# LPC1115_4TE_TOP_V1_0.net
KiCad netlist of a schematic drawn in EAGLE
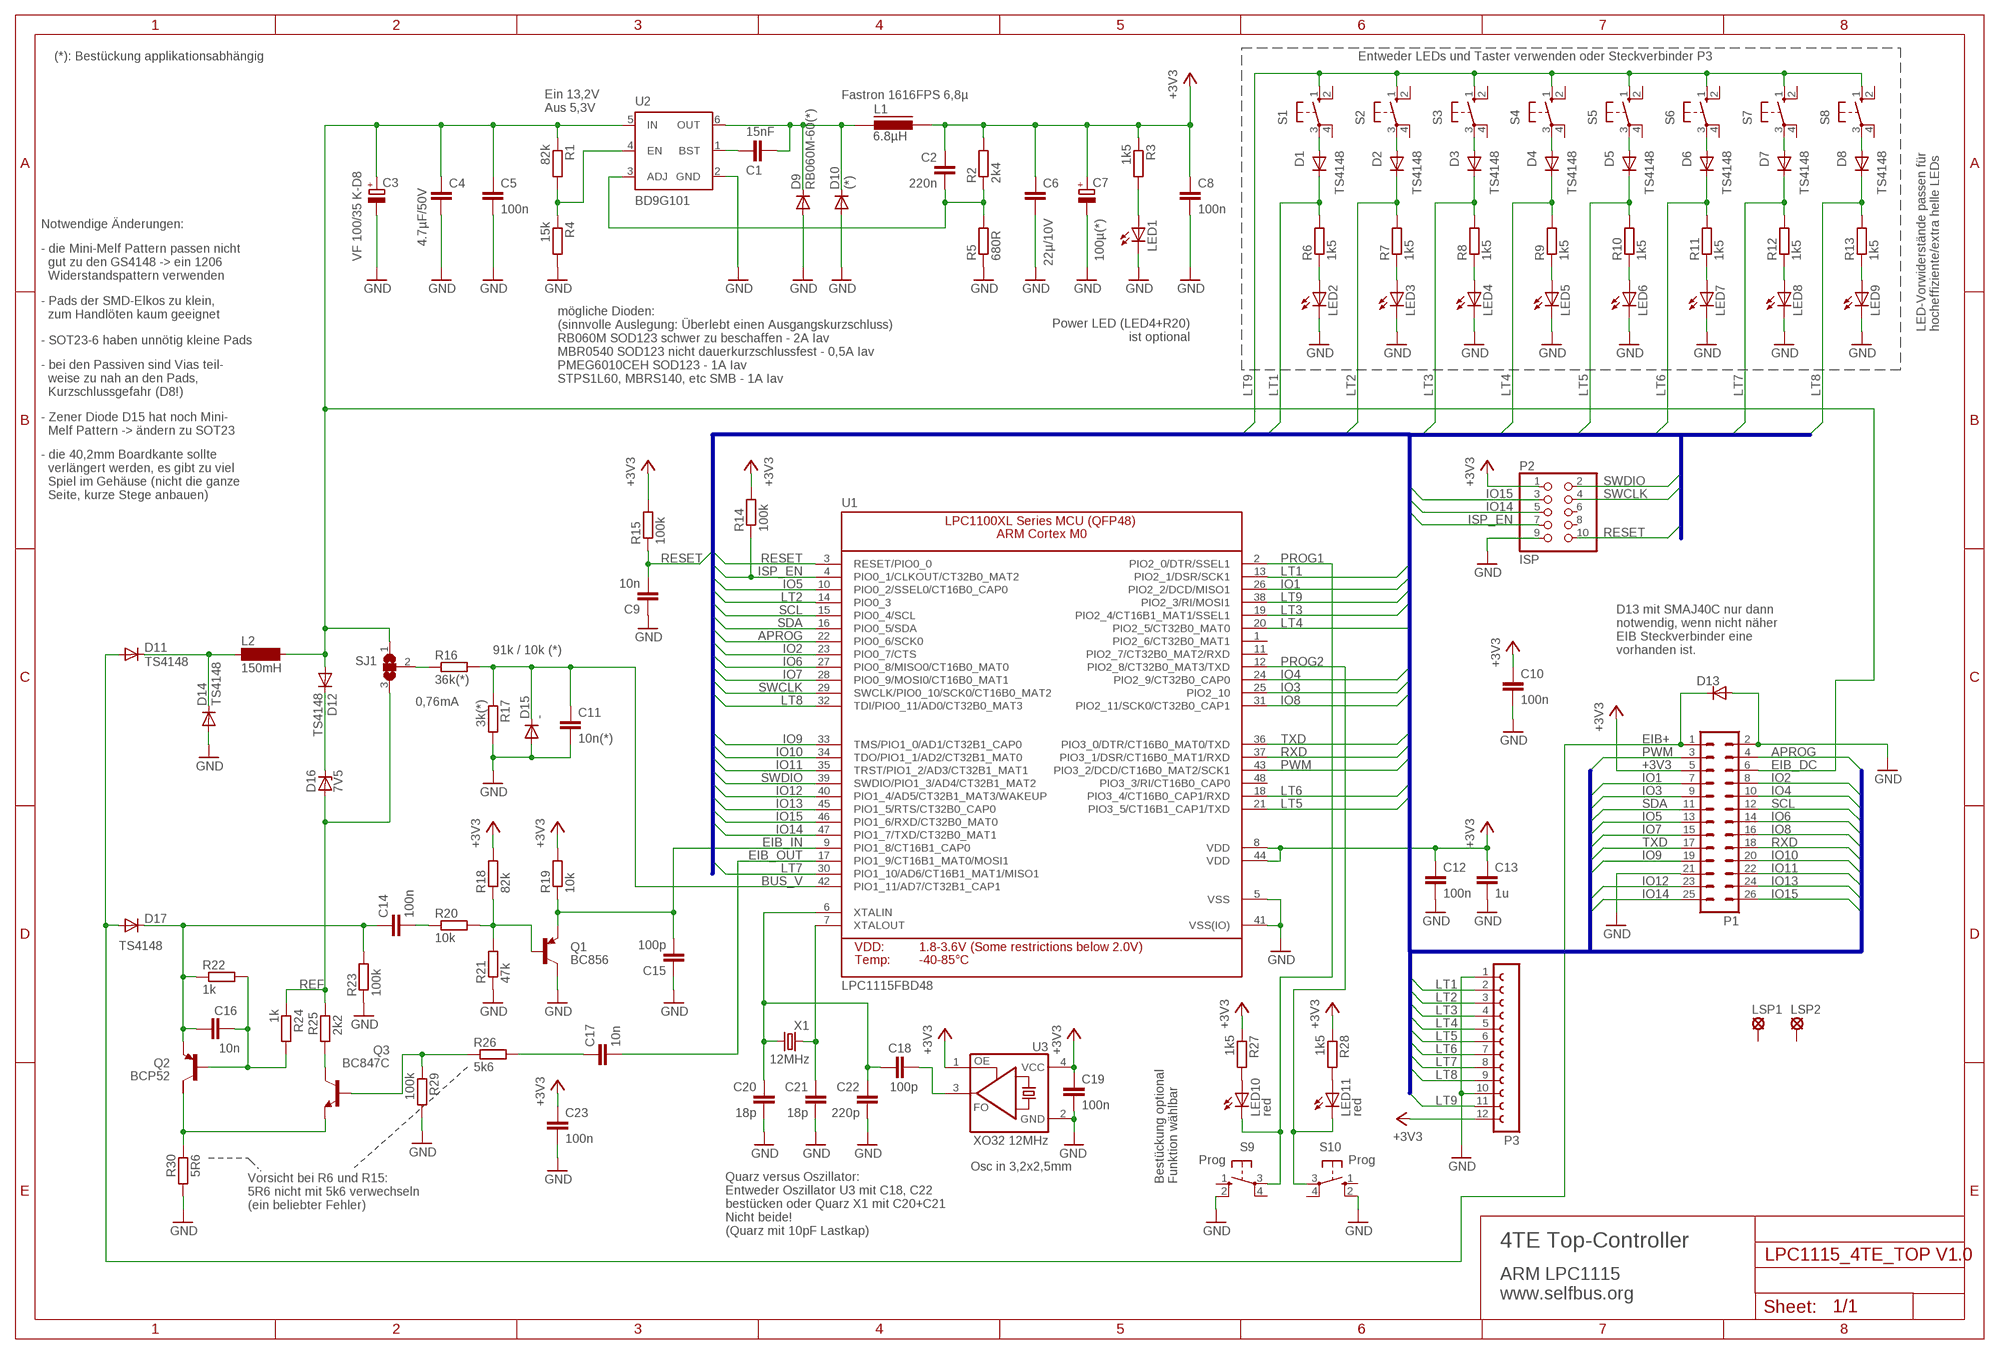
[diagram p0: schematic, sheet 1]

(export (version "E")
  (design (tool "Eeschema 10.0.6"))
  (components
    (comp (ref "C1")
      (value "15nF")
      (footprint "eagle-import:R0805M")
      (libsource (lib "eagle-import") (part "C-EUC0805M"))
    )
    (comp (ref "C2")
      (value "220n")
      (footprint "eagle-import:R0805M")
      (libsource (lib "eagle-import") (part "C-EUC0805M"))
    )
    (comp (ref "C3")
      (value "VF 100/35 K-D8")
      (footprint "eagle-import:UD-6,3X7,7_NICHICON")
      (libsource (lib "eagle-import") (part "CPOL-EUUD-6,3X7,7"))
    )
    (comp (ref "C4")
      (value "4.7µF/50V")
      (footprint "eagle-import:R1206M")
      (libsource (lib "eagle-import") (part "C-EUC1206M"))
    )
    (comp (ref "C5")
      (value "100n")
      (footprint "eagle-import:R0805M")
      (libsource (lib "eagle-import") (part "C-EUC0805M"))
    )
    (comp (ref "C6")
      (value "22µ/10V")
      (footprint "eagle-import:C1210K")
      (libsource (lib "eagle-import") (part "C-EUC1210K"))
    )
    (comp (ref "C7")
      (value "100µ(*)")
      (footprint "eagle-import:UD-6,3X7,7_NICHICON")
      (libsource (lib "eagle-import") (part "CPOL-EUUD-6,3X7,7"))
    )
    (comp (ref "C8")
      (value "100n")
      (footprint "eagle-import:R0805M")
      (libsource (lib "eagle-import") (part "C-EUC0805M"))
    )
    (comp (ref "C9")
      (value "10n")
      (footprint "eagle-import:R0805M")
      (libsource (lib "eagle-import") (part "C-EUC0805M"))
    )
    (comp (ref "C10")
      (value "100n")
      (footprint "eagle-import:R0805M")
      (libsource (lib "eagle-import") (part "C-EUC0805M"))
    )
    (comp (ref "C11")
      (value "10n(*)")
      (footprint "eagle-import:R0805M")
      (libsource (lib "eagle-import") (part "C-EUC0805M"))
    )
    (comp (ref "C12")
      (value "100n")
      (footprint "eagle-import:R0805M")
      (libsource (lib "eagle-import") (part "C-EUC0805M"))
    )
    (comp (ref "C13")
      (value "1u")
      (footprint "eagle-import:R0805M")
      (libsource (lib "eagle-import") (part "C-EUC0805M"))
    )
    (comp (ref "C14")
      (value "100n")
      (footprint "eagle-import:R0805M")
      (libsource (lib "eagle-import") (part "C-EUC0805M"))
    )
    (comp (ref "C15")
      (value "100p")
      (footprint "eagle-import:R0805M")
      (libsource (lib "eagle-import") (part "C-EUC0805M"))
    )
    (comp (ref "C16")
      (value "10n")
      (footprint "eagle-import:R0805M")
      (libsource (lib "eagle-import") (part "C-EUC0805M"))
    )
    (comp (ref "C17")
      (value "10n")
      (footprint "eagle-import:R0805M")
      (libsource (lib "eagle-import") (part "C-EUC0805M"))
    )
    (comp (ref "C18")
      (value "100p")
      (footprint "eagle-import:R0805M")
      (libsource (lib "eagle-import") (part "C-EUC0805M"))
    )
    (comp (ref "C19")
      (value "100n")
      (footprint "eagle-import:R0805M")
      (libsource (lib "eagle-import") (part "C-EUC0805M"))
    )
    (comp (ref "C20")
      (value "18p")
      (footprint "eagle-import:R0805M")
      (libsource (lib "eagle-import") (part "C-EUC0805M"))
    )
    (comp (ref "C21")
      (value "18p")
      (footprint "eagle-import:R0805M")
      (libsource (lib "eagle-import") (part "C-EUC0805M"))
    )
    (comp (ref "C22")
      (value "220p")
      (footprint "eagle-import:R0805M")
      (libsource (lib "eagle-import") (part "C-EUC0805M"))
    )
    (comp (ref "C23")
      (value "100n")
      (footprint "eagle-import:R0805M")
      (libsource (lib "eagle-import") (part "C-EUC0805M"))
    )
    (comp (ref "D1")
      (value "TS4148")
      (footprint "eagle-import:MINIMELF")
      (libsource (lib "eagle-import") (part "DIODE-MINIMELF"))
    )
    (comp (ref "D2")
      (value "TS4148")
      (footprint "eagle-import:MINIMELF")
      (libsource (lib "eagle-import") (part "DIODE-MINIMELF"))
    )
    (comp (ref "D3")
      (value "TS4148")
      (footprint "eagle-import:MINIMELF")
      (libsource (lib "eagle-import") (part "DIODE-MINIMELF"))
    )
    (comp (ref "D4")
      (value "TS4148")
      (footprint "eagle-import:MINIMELF")
      (libsource (lib "eagle-import") (part "DIODE-MINIMELF"))
    )
    (comp (ref "D5")
      (value "TS4148")
      (footprint "eagle-import:MINIMELF")
      (libsource (lib "eagle-import") (part "DIODE-MINIMELF"))
    )
    (comp (ref "D6")
      (value "TS4148")
      (footprint "eagle-import:MINIMELF")
      (libsource (lib "eagle-import") (part "DIODE-MINIMELF"))
    )
    (comp (ref "D7")
      (value "TS4148")
      (footprint "eagle-import:MINIMELF")
      (libsource (lib "eagle-import") (part "DIODE-MINIMELF"))
    )
    (comp (ref "D8")
      (value "TS4148")
      (footprint "eagle-import:MINIMELF")
      (libsource (lib "eagle-import") (part "DIODE-MINIMELF"))
    )
    (comp (ref "D9")
      (value "RB060M-60(*)")
      (footprint "eagle-import:SOD123")
      (libsource (lib "eagle-import") (part "DIODE-SOD123"))
    )
    (comp (ref "D10")
      (value "(*)")
      (footprint "eagle-import:SMB")
      (libsource (lib "eagle-import") (part "DIODE-SMB"))
    )
    (comp (ref "D11")
      (value "TS4148")
      (footprint "eagle-import:MINIMELF")
      (libsource (lib "eagle-import") (part "DIODE-MINIMELF"))
    )
    (comp (ref "D12")
      (value "TS4148")
      (footprint "eagle-import:MINIMELF")
      (libsource (lib "eagle-import") (part "DIODE-MINIMELF"))
    )
    (comp (ref "D13")
      (value "D-SMB")
      (footprint "eagle-import:SMB")
      (libsource (lib "eagle-import") (part "D-SMB"))
    )
    (comp (ref "D14")
      (value "TS4148")
      (footprint "eagle-import:MINIMELF")
      (libsource (lib "eagle-import") (part "DIODE-MINIMELF"))
    )
    (comp (ref "D15")
      (value "-")
      (footprint "eagle-import:MINIMELF")
      (libsource (lib "eagle-import") (part "DIODE-MINIMELF"))
    )
    (comp (ref "D16")
      (value "7V5")
      (footprint "eagle-import:SOT23")
      (libsource (lib "eagle-import") (part "ZENER-DIODESOT23"))
    )
    (comp (ref "D17")
      (value "TS4148")
      (footprint "eagle-import:MINIMELF")
      (libsource (lib "eagle-import") (part "DIODE-MINIMELF"))
    )
    (comp (ref "L1")
      (value "6.8µH")
      (footprint "eagle-import:1616FPS")
      (libsource (lib "eagle-import") (part "IND_FASTRON_1616FPSB"))
    )
    (comp (ref "L2")
      (value "150mH")
      (footprint "eagle-import:BS11_LIEGEND")
      (libsource (lib "eagle-import") (part "SD12BS11_LIEGEND"))
    )
    (comp (ref "LED1")
      (value "LEDSMT1206")
      (footprint "eagle-import:1206")
      (libsource (lib "eagle-import") (part "LEDSMT1206"))
    )
    (comp (ref "LED2")
      (value "LEDSMT1206")
      (footprint "eagle-import:1206")
      (libsource (lib "eagle-import") (part "LEDSMT1206"))
    )
    (comp (ref "LED3")
      (value "LEDSMT1206")
      (footprint "eagle-import:1206")
      (libsource (lib "eagle-import") (part "LEDSMT1206"))
    )
    (comp (ref "LED4")
      (value "LEDSMT1206")
      (footprint "eagle-import:1206")
      (libsource (lib "eagle-import") (part "LEDSMT1206"))
    )
    (comp (ref "LED5")
      (value "LEDSMT1206")
      (footprint "eagle-import:1206")
      (libsource (lib "eagle-import") (part "LEDSMT1206"))
    )
    (comp (ref "LED6")
      (value "LEDSMT1206")
      (footprint "eagle-import:1206")
      (libsource (lib "eagle-import") (part "LEDSMT1206"))
    )
    (comp (ref "LED7")
      (value "LEDSMT1206")
      (footprint "eagle-import:1206")
      (libsource (lib "eagle-import") (part "LEDSMT1206"))
    )
    (comp (ref "LED8")
      (value "LEDSMT1206")
      (footprint "eagle-import:1206")
      (libsource (lib "eagle-import") (part "LEDSMT1206"))
    )
    (comp (ref "LED9")
      (value "LEDSMT1206")
      (footprint "eagle-import:1206")
      (libsource (lib "eagle-import") (part "LEDSMT1206"))
    )
    (comp (ref "LED10")
      (value "red")
      (footprint "eagle-import:1206")
      (libsource (lib "eagle-import") (part "LEDSMT1206"))
    )
    (comp (ref "LED11")
      (value "red")
      (footprint "eagle-import:1206")
      (libsource (lib "eagle-import") (part "LEDSMT1206"))
    )
    (comp (ref "LSP1")
      (value "SE13_SM")
      (footprint "eagle-import:SE13_SM")
      (libsource (lib "eagle-import") (part "SE13_SM"))
    )
    (comp (ref "LSP2")
      (value "SE13_SM")
      (footprint "eagle-import:SE13_SM")
      (libsource (lib "eagle-import") (part "SE13_SM"))
    )
    (comp (ref "P1")
      (value "ML26")
      (footprint "eagle-import:ML26")
      (libsource (lib "eagle-import") (part "ML26"))
    )
    (comp (ref "P2")
      (value "ISP")
      (footprint "eagle-import:2X05M")
      (libsource (lib "eagle-import") (part "PINHD-2X05_2.00"))
    )
    (comp (ref "P3")
      (value "FE12-1")
      (footprint "eagle-import:FE12")
      (libsource (lib "eagle-import") (part "FE12-1"))
    )
    (comp (ref "Q1")
      (value "BC856")
      (footprint "eagle-import:SOT23-BEC")
      (libsource (lib "eagle-import") (part "BC856SMDB"))
    )
    (comp (ref "Q2")
      (value "BCP52")
      (footprint "eagle-import:SOT223")
      (libsource (lib "eagle-import") (part "FZT753SMD"))
    )
    (comp (ref "Q3")
      (value "BC847C")
      (footprint "eagle-import:SOT23")
      (libsource (lib "eagle-import") (part "BC847"))
    )
    (comp (ref "R1")
      (value "82k")
      (footprint "eagle-import:R0805M")
      (libsource (lib "eagle-import") (part "R-EU_R0805M"))
    )
    (comp (ref "R2")
      (value "2k4")
      (footprint "eagle-import:R0805M")
      (libsource (lib "eagle-import") (part "R-EU_R0805M"))
    )
    (comp (ref "R3")
      (value "1k5")
      (footprint "eagle-import:R0805M")
      (libsource (lib "eagle-import") (part "R-EU_R0805M"))
    )
    (comp (ref "R4")
      (value "15k")
      (footprint "eagle-import:R0805M")
      (libsource (lib "eagle-import") (part "R-EU_R0805M"))
    )
    (comp (ref "R5")
      (value "680R")
      (footprint "eagle-import:R0805M")
      (libsource (lib "eagle-import") (part "R-EU_R0805M"))
    )
    (comp (ref "R6")
      (value "1k5")
      (footprint "eagle-import:R0805M")
      (libsource (lib "eagle-import") (part "R-EU_R0805M"))
    )
    (comp (ref "R7")
      (value "1k5")
      (footprint "eagle-import:R0805M")
      (libsource (lib "eagle-import") (part "R-EU_R0805M"))
    )
    (comp (ref "R8")
      (value "1k5")
      (footprint "eagle-import:R0805M")
      (libsource (lib "eagle-import") (part "R-EU_R0805M"))
    )
    (comp (ref "R9")
      (value "1k5")
      (footprint "eagle-import:R0805M")
      (libsource (lib "eagle-import") (part "R-EU_R0805M"))
    )
    (comp (ref "R10")
      (value "1k5")
      (footprint "eagle-import:R0805M")
      (libsource (lib "eagle-import") (part "R-EU_R0805M"))
    )
    (comp (ref "R11")
      (value "1k5")
      (footprint "eagle-import:R0805M")
      (libsource (lib "eagle-import") (part "R-EU_R0805M"))
    )
    (comp (ref "R12")
      (value "1k5")
      (footprint "eagle-import:R0805M")
      (libsource (lib "eagle-import") (part "R-EU_R0805M"))
    )
    (comp (ref "R13")
      (value "1k5")
      (footprint "eagle-import:R0805M")
      (libsource (lib "eagle-import") (part "R-EU_R0805M"))
    )
    (comp (ref "R14")
      (value "100k")
      (footprint "eagle-import:R0805M")
      (libsource (lib "eagle-import") (part "R-EU_R0805M"))
    )
    (comp (ref "R15")
      (value "100k")
      (footprint "eagle-import:R0805M")
      (libsource (lib "eagle-import") (part "R-EU_R0805M"))
    )
    (comp (ref "R16")
      (value "36k(*)")
      (footprint "eagle-import:R0805M")
      (libsource (lib "eagle-import") (part "R-EU_R0805M"))
    )
    (comp (ref "R17")
      (value "3k(*)")
      (footprint "eagle-import:R0805M")
      (libsource (lib "eagle-import") (part "R-EU_R0805M"))
    )
    (comp (ref "R18")
      (value "82k")
      (footprint "eagle-import:R0805M")
      (libsource (lib "eagle-import") (part "R-EU_R0805M"))
    )
    (comp (ref "R19")
      (value "10k")
      (footprint "eagle-import:R0805M")
      (libsource (lib "eagle-import") (part "R-EU_R0805M"))
    )
    (comp (ref "R20")
      (value "10k")
      (footprint "eagle-import:R0805M")
      (libsource (lib "eagle-import") (part "R-EU_R0805M"))
    )
    (comp (ref "R21")
      (value "47k")
      (footprint "eagle-import:R0805M")
      (libsource (lib "eagle-import") (part "R-EU_R0805M"))
    )
    (comp (ref "R22")
      (value "1k")
      (footprint "eagle-import:R0805M")
      (libsource (lib "eagle-import") (part "R-EU_R0805M"))
    )
    (comp (ref "R23")
      (value "100k")
      (footprint "eagle-import:R0805M")
      (libsource (lib "eagle-import") (part "R-EU_R0805M"))
    )
    (comp (ref "R24")
      (value "1k")
      (footprint "eagle-import:R0805M")
      (libsource (lib "eagle-import") (part "R-EU_R0805M"))
    )
    (comp (ref "R25")
      (value "2k2")
      (footprint "eagle-import:R0805M")
      (libsource (lib "eagle-import") (part "R-EU_R0805M"))
    )
    (comp (ref "R26")
      (value "5k6")
      (footprint "eagle-import:R0805M")
      (libsource (lib "eagle-import") (part "R-EU_R0805M"))
    )
    (comp (ref "R27")
      (value "1k5")
      (footprint "eagle-import:R0805M")
      (libsource (lib "eagle-import") (part "R-EU_R0805M"))
    )
    (comp (ref "R28")
      (value "1k5")
      (footprint "eagle-import:R0805M")
      (libsource (lib "eagle-import") (part "R-EU_R0805M"))
    )
    (comp (ref "R29")
      (value "100k")
      (footprint "eagle-import:R0805M")
      (libsource (lib "eagle-import") (part "R-EU_R0805M"))
    )
    (comp (ref "R30")
      (value "5R6")
      (footprint "eagle-import:R1206M")
      (libsource (lib "eagle-import") (part "R-EU_R1206M"))
    )
    (comp (ref "S1")
      (value "10-XXSMD")
      (footprint "eagle-import:B3F-10XX_SMD")
      (libsource (lib "eagle-import") (part "10-XXSMD"))
    )
    (comp (ref "S2")
      (value "10-XXSMD")
      (footprint "eagle-import:B3F-10XX_SMD")
      (libsource (lib "eagle-import") (part "10-XXSMD"))
    )
    (comp (ref "S3")
      (value "10-XXSMD")
      (footprint "eagle-import:B3F-10XX_SMD")
      (libsource (lib "eagle-import") (part "10-XXSMD"))
    )
    (comp (ref "S4")
      (value "10-XXSMD")
      (footprint "eagle-import:B3F-10XX_SMD")
      (libsource (lib "eagle-import") (part "10-XXSMD"))
    )
    (comp (ref "S5")
      (value "10-XXSMD")
      (footprint "eagle-import:B3F-10XX_SMD")
      (libsource (lib "eagle-import") (part "10-XXSMD"))
    )
    (comp (ref "S6")
      (value "10-XXSMD")
      (footprint "eagle-import:B3F-10XX_SMD")
      (libsource (lib "eagle-import") (part "10-XXSMD"))
    )
    (comp (ref "S7")
      (value "10-XXSMD")
      (footprint "eagle-import:B3F-10XX_SMD")
      (libsource (lib "eagle-import") (part "10-XXSMD"))
    )
    (comp (ref "S8")
      (value "10-XXSMD")
      (footprint "eagle-import:B3F-10XX_SMD")
      (libsource (lib "eagle-import") (part "10-XXSMD"))
    )
    (comp (ref "S9")
      (value "Prog")
      (footprint "eagle-import:B3F-10XX_SMD")
      (libsource (lib "eagle-import") (part "10-XXSMD"))
    )
    (comp (ref "S10")
      (value "Prog")
      (footprint "eagle-import:B3F-10XX_SMD")
      (libsource (lib "eagle-import") (part "10-XXSMD"))
    )
    (comp (ref "SJ1")
      (value "SJ2W")
      (footprint "eagle-import:SJ_2")
      (libsource (lib "eagle-import") (part "SJ2W"))
    )
    (comp (ref "U1")
      (value "LPC1115FBD48")
      (footprint "eagle-import:LQFP48")
      (libsource (lib "eagle-import") (part "LPC1113/4/5_QFP48_XLSERIES"))
    )
    (comp (ref "U2")
      (value "BD9G101")
      (footprint "eagle-import:SOT23-6")
      (libsource (lib "eagle-import") (part "BD9G101GBD9G101G-SOT23-6"))
    )
    (comp (ref "U3")
      (value "XO32 12MHz")
      (footprint "eagle-import:ASF")
      (libsource (lib "eagle-import") (part "ASFL"))
    )
    (comp (ref "X1")
      (value "12MHz")
      (footprint "eagle-import:ASF")
      (libsource (lib "eagle-import") (part "CRYSTALASF"))
    )
  )
  (nets
    (net (code "1") (name "+3V3") (class "Default")
      (node (ref "C10") (pin "1") (pinfunction "1_1") (pintype "passive"))
      (node (ref "C12") (pin "1") (pinfunction "1_1") (pintype "passive"))
      (node (ref "C13") (pin "1") (pinfunction "1_1") (pintype "passive"))
      (node (ref "C19") (pin "1") (pinfunction "1_1") (pintype "passive"))
      (node (ref "C2") (pin "1") (pinfunction "1_1") (pintype "passive"))
      (node (ref "C23") (pin "1") (pinfunction "1_1") (pintype "passive"))
      (node (ref "C6") (pin "1") (pinfunction "1_1") (pintype "passive"))
      (node (ref "C7") (pin "+") (pinfunction "+_+") (pintype "passive"))
      (node (ref "C8") (pin "1") (pinfunction "1_1") (pintype "passive"))
      (node (ref "L1") (pin "P$2") (pinfunction "2_P$2") (pintype "passive"))
      (node (ref "P1") (pin "5") (pinfunction "5_5") (pintype "passive"))
      (node (ref "P2") (pin "1") (pinfunction "1_1") (pintype "passive"))
      (node (ref "P3") (pin "12") (pinfunction "12_12") (pintype "passive"))
      (node (ref "R14") (pin "2") (pinfunction "2_2") (pintype "passive"))
      (node (ref "R15") (pin "2") (pinfunction "2_2") (pintype "passive"))
      (node (ref "R18") (pin "2") (pinfunction "2_2") (pintype "passive"))
      (node (ref "R19") (pin "2") (pinfunction "2_2") (pintype "passive"))
      (node (ref "R2") (pin "2") (pinfunction "2_2") (pintype "passive"))
      (node (ref "R27") (pin "1") (pinfunction "1_1") (pintype "passive"))
      (node (ref "R28") (pin "1") (pinfunction "1_1") (pintype "passive"))
      (node (ref "R3") (pin "1") (pinfunction "1_1") (pintype "passive"))
      (node (ref "U1") (pin "44") (pinfunction "VDD_44") (pintype "power_in"))
      (node (ref "U1") (pin "8") (pinfunction "VDD_8") (pintype "power_in"))
      (node (ref "U3") (pin "1") (pinfunction "OE_1") (pintype "input"))
      (node (ref "U3") (pin "4") (pinfunction "VCC_4") (pintype "power_in"))
    )
    (net (code "2") (name "/APROG") (class "Default")
      (node (ref "P1") (pin "4") (pinfunction "4_4") (pintype "passive"))
      (node (ref "U1") (pin "22") (pinfunction "PIO0_6/SCK0_22") (pintype "bidirectional"))
    )
    (net (code "3") (name "/BUS_V") (class "Default")
      (node (ref "C11") (pin "1") (pinfunction "1_1") (pintype "passive"))
      (node (ref "D15") (pin "C") (pinfunction "C_C") (pintype "passive"))
      (node (ref "R16") (pin "2") (pinfunction "2_2") (pintype "passive"))
      (node (ref "R17") (pin "1") (pinfunction "1_1") (pintype "passive"))
      (node (ref "U1") (pin "42") (pinfunction "PIO1_11/AD7/CT32B1_CAP1_42") (pintype "bidirectional"))
    )
    (net (code "4") (name "/EIB+") (class "Default")
      (node (ref "D11") (pin "A") (pinfunction "A_A") (pintype "passive"))
      (node (ref "D13") (pin "1") (pinfunction "C_1") (pintype "passive"))
      (node (ref "D17") (pin "A") (pinfunction "A_A") (pintype "passive"))
      (node (ref "P1") (pin "1") (pinfunction "1_1") (pintype "passive"))
    )
    (net (code "5") (name "/EIB_DC") (class "Default")
      (node (ref "C3") (pin "+") (pinfunction "+_+") (pintype "passive"))
      (node (ref "C4") (pin "1") (pinfunction "1_1") (pintype "passive"))
      (node (ref "C5") (pin "1") (pinfunction "1_1") (pintype "passive"))
      (node (ref "D12") (pin "A") (pinfunction "A_A") (pintype "passive"))
      (node (ref "L2") (pin "2") (pinfunction "2_2") (pintype "passive"))
      (node (ref "P1") (pin "6") (pinfunction "6_6") (pintype "passive"))
      (node (ref "R1") (pin "1") (pinfunction "1_1") (pintype "passive"))
      (node (ref "SJ1") (pin "1") (pinfunction "1_1") (pintype "passive"))
      (node (ref "U2") (pin "5") (pinfunction "IN_5") (pintype "input"))
    )
    (net (code "6") (name "/EIB_IN") (class "Default")
      (node (ref "C15") (pin "2") (pinfunction "2_2") (pintype "passive"))
      (node (ref "Q1") (pin "E") (pinfunction "E_E") (pintype "passive"))
      (node (ref "R19") (pin "1") (pinfunction "1_1") (pintype "passive"))
      (node (ref "U1") (pin "9") (pinfunction "PIO1_8/CT16B1_CAP0_9") (pintype "bidirectional"))
    )
    (net (code "7") (name "/EIB_OUT") (class "Default")
      (node (ref "C17") (pin "2") (pinfunction "2_2") (pintype "passive"))
      (node (ref "U1") (pin "17") (pinfunction "PIO1_9/CT16B1_MAT0/MOSI1_17") (pintype "bidirectional"))
    )
    (net (code "8") (name "/IO1") (class "Default")
      (node (ref "P1") (pin "7") (pinfunction "7_7") (pintype "passive"))
      (node (ref "U1") (pin "26") (pinfunction "PIO2_2/DCD/MISO1_26") (pintype "bidirectional"))
    )
    (net (code "9") (name "/IO2") (class "Default")
      (node (ref "P1") (pin "8") (pinfunction "8_8") (pintype "passive"))
      (node (ref "U1") (pin "23") (pinfunction "PIO0_7/CTS_23") (pintype "bidirectional"))
    )
    (net (code "10") (name "/IO3") (class "Default")
      (node (ref "P1") (pin "9") (pinfunction "9_9") (pintype "passive"))
      (node (ref "U1") (pin "25") (pinfunction "PIO2_10_25") (pintype "bidirectional"))
    )
    (net (code "11") (name "/IO4") (class "Default")
      (node (ref "P1") (pin "10") (pinfunction "10_10") (pintype "passive"))
      (node (ref "U1") (pin "24") (pinfunction "PIO2_9/CT32B0_CAP0_24") (pintype "bidirectional"))
    )
    (net (code "12") (name "/IO5") (class "Default")
      (node (ref "P1") (pin "13") (pinfunction "13_13") (pintype "passive"))
      (node (ref "U1") (pin "10") (pinfunction "PIO0_2/SSEL0/CT16B0_CAP0_10") (pintype "bidirectional"))
    )
    (net (code "13") (name "/IO6") (class "Default")
      (node (ref "P1") (pin "14") (pinfunction "14_14") (pintype "passive"))
      (node (ref "U1") (pin "27") (pinfunction "PIO0_8/MISO0/CT16B0_MAT0_27") (pintype "bidirectional"))
    )
    (net (code "14") (name "/IO7") (class "Default")
      (node (ref "P1") (pin "15") (pinfunction "15_15") (pintype "passive"))
      (node (ref "U1") (pin "28") (pinfunction "PIO0_9/MOSI0/CT16B0_MAT1_28") (pintype "bidirectional"))
    )
    (net (code "15") (name "/IO8") (class "Default")
      (node (ref "P1") (pin "16") (pinfunction "16_16") (pintype "passive"))
      (node (ref "U1") (pin "31") (pinfunction "PIO2_11/SCK0/CT32B0_CAP1_31") (pintype "bidirectional"))
    )
    (net (code "16") (name "/IO9") (class "Default")
      (node (ref "P1") (pin "19") (pinfunction "19_19") (pintype "passive"))
      (node (ref "U1") (pin "33") (pinfunction "TMS/PIO1_0/AD1/CT32B1_CAP0_33") (pintype "bidirectional"))
    )
    (net (code "17") (name "/IO10") (class "Default")
      (node (ref "P1") (pin "20") (pinfunction "20_20") (pintype "passive"))
      (node (ref "U1") (pin "34") (pinfunction "TDO/PIO1_1/AD2/CT32B1_MAT0_34") (pintype "bidirectional"))
    )
    (net (code "18") (name "/IO11") (class "Default")
      (node (ref "P1") (pin "22") (pinfunction "22_22") (pintype "passive"))
      (node (ref "U1") (pin "35") (pinfunction "TRST/PIO1_2/AD3/CT32B1_MAT1_35") (pintype "bidirectional"))
    )
    (net (code "19") (name "/IO12") (class "Default")
      (node (ref "P1") (pin "23") (pinfunction "23_23") (pintype "passive"))
      (node (ref "U1") (pin "40") (pinfunction "PIO1_4/AD5/CT32B1_MAT3/WAKEUP_40") (pintype "bidirectional"))
    )
    (net (code "20") (name "/IO13") (class "Default")
      (node (ref "P1") (pin "24") (pinfunction "24_24") (pintype "passive"))
      (node (ref "U1") (pin "45") (pinfunction "PIO1_5/RTS/CT32B0_CAP0_45") (pintype "bidirectional"))
    )
    (net (code "21") (name "/IO14") (class "Default")
      (node (ref "P1") (pin "25") (pinfunction "25_25") (pintype "passive"))
      (node (ref "P2") (pin "5") (pinfunction "5_5") (pintype "passive"))
      (node (ref "U1") (pin "47") (pinfunction "PIO1_7/TXD/CT32B0_MAT1_47") (pintype "bidirectional"))
    )
    (net (code "22") (name "/IO15") (class "Default")
      (node (ref "P1") (pin "26") (pinfunction "26_26") (pintype "passive"))
      (node (ref "P2") (pin "3") (pinfunction "3_3") (pintype "passive"))
      (node (ref "U1") (pin "46") (pinfunction "PIO1_6/RXD/CT32B0_MAT0_46") (pintype "bidirectional"))
    )
    (net (code "23") (name "/ISP_EN") (class "Default")
      (node (ref "P2") (pin "7") (pinfunction "7_7") (pintype "passive"))
      (node (ref "R14") (pin "1") (pinfunction "1_1") (pintype "passive"))
      (node (ref "U1") (pin "4") (pinfunction "PIO0_1/CLKOUT/CT32B0_MAT2_4") (pintype "bidirectional"))
    )
    (net (code "24") (name "/LT1") (class "Default")
      (node (ref "D1") (pin "C") (pinfunction "C_C") (pintype "passive"))
      (node (ref "P3") (pin "2") (pinfunction "2_2") (pintype "passive"))
      (node (ref "R6") (pin "2") (pinfunction "2_2") (pintype "passive"))
      (node (ref "U1") (pin "13") (pinfunction "PIO2_1/DSR/SCK1_13") (pintype "bidirectional"))
    )
    (net (code "25") (name "/LT2") (class "Default")
      (node (ref "D2") (pin "C") (pinfunction "C_C") (pintype "passive"))
      (node (ref "P3") (pin "3") (pinfunction "3_3") (pintype "passive"))
      (node (ref "R7") (pin "2") (pinfunction "2_2") (pintype "passive"))
      (node (ref "U1") (pin "14") (pinfunction "PIO0_3_14") (pintype "bidirectional"))
    )
    (net (code "26") (name "/LT3") (class "Default")
      (node (ref "D3") (pin "C") (pinfunction "C_C") (pintype "passive"))
      (node (ref "P3") (pin "4") (pinfunction "4_4") (pintype "passive"))
      (node (ref "R8") (pin "2") (pinfunction "2_2") (pintype "passive"))
      (node (ref "U1") (pin "19") (pinfunction "PIO2_4/CT16B1_MAT1/SSEL1_19") (pintype "bidirectional"))
    )
    (net (code "27") (name "/LT4") (class "Default")
      (node (ref "D4") (pin "C") (pinfunction "C_C") (pintype "passive"))
      (node (ref "P3") (pin "5") (pinfunction "5_5") (pintype "passive"))
      (node (ref "R9") (pin "2") (pinfunction "2_2") (pintype "passive"))
      (node (ref "U1") (pin "20") (pinfunction "PIO2_5/CT32B0_MAT0_20") (pintype "bidirectional"))
    )
    (net (code "28") (name "/LT5") (class "Default")
      (node (ref "D5") (pin "C") (pinfunction "C_C") (pintype "passive"))
      (node (ref "P3") (pin "6") (pinfunction "6_6") (pintype "passive"))
      (node (ref "R10") (pin "2") (pinfunction "2_2") (pintype "passive"))
      (node (ref "U1") (pin "21") (pinfunction "PIO3_5/CT16B1_CAP1/TXD_21") (pintype "bidirectional"))
    )
    (net (code "29") (name "/LT6") (class "Default")
      (node (ref "D6") (pin "C") (pinfunction "C_C") (pintype "passive"))
      (node (ref "P3") (pin "7") (pinfunction "7_7") (pintype "passive"))
      (node (ref "R11") (pin "2") (pinfunction "2_2") (pintype "passive"))
      (node (ref "U1") (pin "18") (pinfunction "PIO3_4/CT16B0_CAP1/RXD_18") (pintype "bidirectional"))
    )
    (net (code "30") (name "/LT7") (class "Default")
      (node (ref "D7") (pin "C") (pinfunction "C_C") (pintype "passive"))
      (node (ref "P3") (pin "8") (pinfunction "8_8") (pintype "passive"))
      (node (ref "R12") (pin "2") (pinfunction "2_2") (pintype "passive"))
      (node (ref "U1") (pin "30") (pinfunction "PIO1_10/AD6/CT16B1_MAT1/MISO1_30") (pintype "bidirectional"))
    )
    (net (code "31") (name "/LT8") (class "Default")
      (node (ref "D8") (pin "C") (pinfunction "C_C") (pintype "passive"))
      (node (ref "P3") (pin "9") (pinfunction "9_9") (pintype "passive"))
      (node (ref "R13") (pin "2") (pinfunction "2_2") (pintype "passive"))
      (node (ref "U1") (pin "32") (pinfunction "TDI/PIO0_11/AD0/CT32B0_MAT3_32") (pintype "bidirectional"))
    )
    (net (code "32") (name "/LT9") (class "Default")
      (node (ref "P3") (pin "11") (pinfunction "11_11") (pintype "passive"))
      (node (ref "S1") (pin "1") (pinfunction "S_1") (pintype "passive"))
      (node (ref "S2") (pin "1") (pinfunction "S_1") (pintype "passive"))
      (node (ref "S3") (pin "1") (pinfunction "S_1") (pintype "passive"))
      (node (ref "S4") (pin "1") (pinfunction "S_1") (pintype "passive"))
      (node (ref "S5") (pin "1") (pinfunction "S_1") (pintype "passive"))
      (node (ref "S6") (pin "1") (pinfunction "S_1") (pintype "passive"))
      (node (ref "S7") (pin "1") (pinfunction "S_1") (pintype "passive"))
      (node (ref "S8") (pin "1") (pinfunction "S_1") (pintype "passive"))
      (node (ref "U1") (pin "38") (pinfunction "PIO2_3/RI/MOSI1_38") (pintype "bidirectional"))
    )
    (net (code "33") (name "/PROG1") (class "Default")
      (node (ref "LED10") (pin "C") (pinfunction "C_C") (pintype "passive"))
      (node (ref "S9") (pin "3") (pinfunction "P_3") (pintype "passive"))
      (node (ref "U1") (pin "2") (pinfunction "PIO2_0/DTR/SSEL1_2") (pintype "bidirectional"))
    )
    (net (code "34") (name "/PROG2") (class "Default")
      (node (ref "LED11") (pin "C") (pinfunction "C_C") (pintype "passive"))
      (node (ref "S10") (pin "3") (pinfunction "P_3") (pintype "passive"))
      (node (ref "U1") (pin "12") (pinfunction "PIO2_8/CT32B0_MAT3/TXD_12") (pintype "bidirectional"))
    )
    (net (code "35") (name "/PWM") (class "Default")
      (node (ref "P1") (pin "3") (pinfunction "3_3") (pintype "passive"))
      (node (ref "U1") (pin "43") (pinfunction "PIO3_2/DCD/CT16B0_MAT2/SCK1_43") (pintype "bidirectional"))
    )
    (net (code "36") (name "/REF") (class "Default")
      (node (ref "D16") (pin "1") (pinfunction "A_1") (pintype "passive"))
      (node (ref "R24") (pin "1") (pinfunction "1_1") (pintype "passive"))
      (node (ref "R25") (pin "2") (pinfunction "2_2") (pintype "passive"))
      (node (ref "SJ1") (pin "3") (pinfunction "3_3") (pintype "passive"))
    )
    (net (code "37") (name "/RESET") (class "Default")
      (node (ref "C9") (pin "2") (pinfunction "2_2") (pintype "passive"))
      (node (ref "P2") (pin "10") (pinfunction "10_10") (pintype "passive"))
      (node (ref "R15") (pin "1") (pinfunction "1_1") (pintype "passive"))
      (node (ref "U1") (pin "3") (pinfunction "RESET/PIO0_0_3") (pintype "bidirectional"))
    )
    (net (code "38") (name "/RXD") (class "Default")
      (node (ref "P1") (pin "18") (pinfunction "18_18") (pintype "passive"))
      (node (ref "U1") (pin "37") (pinfunction "PIO3_1/DSR/CT16B0_MAT1/RXD_37") (pintype "bidirectional"))
    )
    (net (code "39") (name "/SCL") (class "Default")
      (node (ref "P1") (pin "12") (pinfunction "12_12") (pintype "passive"))
      (node (ref "U1") (pin "15") (pinfunction "PIO0_4/SCL_15") (pintype "bidirectional"))
    )
    (net (code "40") (name "/SDA") (class "Default")
      (node (ref "P1") (pin "11") (pinfunction "11_11") (pintype "passive"))
      (node (ref "U1") (pin "16") (pinfunction "PIO0_5/SDA_16") (pintype "bidirectional"))
    )
    (net (code "41") (name "/SWCLK") (class "Default")
      (node (ref "P2") (pin "4") (pinfunction "4_4") (pintype "passive"))
      (node (ref "U1") (pin "29") (pinfunction "SWCLK/PIO0_10/SCK0/CT16B0_MAT2_29") (pintype "bidirectional"))
    )
    (net (code "42") (name "/SWDIO") (class "Default")
      (node (ref "P2") (pin "2") (pinfunction "2_2") (pintype "passive"))
      (node (ref "U1") (pin "39") (pinfunction "SWDIO/PIO1_3/AD4/CT32B1_MAT2_39") (pintype "bidirectional"))
    )
    (net (code "43") (name "/TXD") (class "Default")
      (node (ref "P1") (pin "17") (pinfunction "17_17") (pintype "passive"))
      (node (ref "U1") (pin "36") (pinfunction "PIO3_0/DTR/CT16B0_MAT0/TXD_36") (pintype "bidirectional"))
    )
    (net (code "44") (name "GND") (class "Default")
      (node (ref "C10") (pin "2") (pinfunction "2_2") (pintype "passive"))
      (node (ref "C11") (pin "2") (pinfunction "2_2") (pintype "passive"))
      (node (ref "C12") (pin "2") (pinfunction "2_2") (pintype "passive"))
      (node (ref "C13") (pin "2") (pinfunction "2_2") (pintype "passive"))
      (node (ref "C15") (pin "1") (pinfunction "1_1") (pintype "passive"))
      (node (ref "C19") (pin "2") (pinfunction "2_2") (pintype "passive"))
      (node (ref "C20") (pin "2") (pinfunction "2_2") (pintype "passive"))
      (node (ref "C21") (pin "2") (pinfunction "2_2") (pintype "passive"))
      (node (ref "C22") (pin "2") (pinfunction "2_2") (pintype "passive"))
      (node (ref "C23") (pin "2") (pinfunction "2_2") (pintype "passive"))
      (node (ref "C3") (pin "-") (pinfunction "-_-") (pintype "passive"))
      (node (ref "C4") (pin "2") (pinfunction "2_2") (pintype "passive"))
      (node (ref "C5") (pin "2") (pinfunction "2_2") (pintype "passive"))
      (node (ref "C6") (pin "2") (pinfunction "2_2") (pintype "passive"))
      (node (ref "C7") (pin "-") (pinfunction "-_-") (pintype "passive"))
      (node (ref "C8") (pin "2") (pinfunction "2_2") (pintype "passive"))
      (node (ref "C9") (pin "1") (pinfunction "1_1") (pintype "passive"))
      (node (ref "D10") (pin "A") (pinfunction "A_A") (pintype "passive"))
      (node (ref "D13") (pin "2") (pinfunction "A_2") (pintype "passive"))
      (node (ref "D14") (pin "A") (pinfunction "A_A") (pintype "passive"))
      (node (ref "D15") (pin "A") (pinfunction "A_A") (pintype "passive"))
      (node (ref "D9") (pin "A") (pinfunction "A_A") (pintype "passive"))
      (node (ref "LED1") (pin "C") (pinfunction "C_C") (pintype "passive"))
      (node (ref "LED2") (pin "C") (pinfunction "C_C") (pintype "passive"))
      (node (ref "LED3") (pin "C") (pinfunction "C_C") (pintype "passive"))
      (node (ref "LED4") (pin "C") (pinfunction "C_C") (pintype "passive"))
      (node (ref "LED5") (pin "C") (pinfunction "C_C") (pintype "passive"))
      (node (ref "LED6") (pin "C") (pinfunction "C_C") (pintype "passive"))
      (node (ref "LED7") (pin "C") (pinfunction "C_C") (pintype "passive"))
      (node (ref "LED8") (pin "C") (pinfunction "C_C") (pintype "passive"))
      (node (ref "LED9") (pin "C") (pinfunction "C_C") (pintype "passive"))
      (node (ref "P1") (pin "2") (pinfunction "2_2") (pintype "passive"))
      (node (ref "P1") (pin "21") (pinfunction "21_21") (pintype "passive"))
      (node (ref "P2") (pin "9") (pinfunction "9_9") (pintype "passive"))
      (node (ref "P3") (pin "1") (pinfunction "1_1") (pintype "passive"))
      (node (ref "P3") (pin "10") (pinfunction "10_10") (pintype "passive"))
      (node (ref "Q1") (pin "C") (pinfunction "C_C") (pintype "passive"))
      (node (ref "R17") (pin "2") (pinfunction "2_2") (pintype "passive"))
      (node (ref "R21") (pin "1") (pinfunction "1_1") (pintype "passive"))
      (node (ref "R23") (pin "1") (pinfunction "1_1") (pintype "passive"))
      (node (ref "R29") (pin "2") (pinfunction "2_2") (pintype "passive"))
      (node (ref "R30") (pin "1") (pinfunction "1_1") (pintype "passive"))
      (node (ref "R4") (pin "2") (pinfunction "2_2") (pintype "passive"))
      (node (ref "R5") (pin "1") (pinfunction "1_1") (pintype "passive"))
      (node (ref "S10") (pin "2") (pinfunction "S1_2") (pintype "passive"))
      (node (ref "S9") (pin "2") (pinfunction "S1_2") (pintype "passive"))
      (node (ref "U1") (pin "41") (pinfunction "VSS(IO)_41") (pintype "power_in"))
      (node (ref "U1") (pin "5") (pinfunction "VSS_5") (pintype "power_in"))
      (node (ref "U2") (pin "2") (pinfunction "GND_2") (pintype "power_in"))
      (node (ref "U3") (pin "2") (pinfunction "GND_2") (pintype "power_in"))
    )
    (net (code "45") (name "Net-(C14-Pad2)") (class "Default")
      (node (ref "C14") (pin "2") (pinfunction "2_2") (pintype "passive"))
      (node (ref "R20") (pin "1") (pinfunction "1_1") (pintype "passive"))
    )
    (net (code "46") (name "Net-(C17-Pad1)") (class "Default")
      (node (ref "C17") (pin "1") (pinfunction "1_1") (pintype "passive"))
      (node (ref "R26") (pin "2") (pinfunction "2_2") (pintype "passive"))
    )
    (net (code "47") (name "Net-(D11-PadC)") (class "Default")
      (node (ref "D11") (pin "C") (pinfunction "C_C") (pintype "passive"))
      (node (ref "D14") (pin "C") (pinfunction "C_C") (pintype "passive"))
      (node (ref "L2") (pin "1") (pinfunction "1_1") (pintype "passive"))
    )
    (net (code "48") (name "Net-(D16-C)") (class "Default")
      (node (ref "D12") (pin "C") (pinfunction "C_C") (pintype "passive"))
      (node (ref "D16") (pin "3") (pinfunction "C_3") (pintype "passive"))
    )
    (net (code "49") (name "Net-(L1-1)") (class "Default")
      (node (ref "C1") (pin "1") (pinfunction "1_1") (pintype "passive"))
      (node (ref "D10") (pin "C") (pinfunction "C_C") (pintype "passive"))
      (node (ref "D9") (pin "C") (pinfunction "C_C") (pintype "passive"))
      (node (ref "L1") (pin "P$1") (pinfunction "1_P$1") (pintype "passive"))
      (node (ref "U2") (pin "6") (pinfunction "OUT_6") (pintype "output"))
    )
    (net (code "50") (name "Net-(LED1-PadA)") (class "Default")
      (node (ref "LED1") (pin "A") (pinfunction "A_A") (pintype "passive"))
      (node (ref "R3") (pin "2") (pinfunction "2_2") (pintype "passive"))
    )
    (net (code "51") (name "Net-(LED2-PadA)") (class "Default")
      (node (ref "LED2") (pin "A") (pinfunction "A_A") (pintype "passive"))
      (node (ref "R6") (pin "1") (pinfunction "1_1") (pintype "passive"))
    )
    (net (code "52") (name "Net-(LED3-PadA)") (class "Default")
      (node (ref "LED3") (pin "A") (pinfunction "A_A") (pintype "passive"))
      (node (ref "R7") (pin "1") (pinfunction "1_1") (pintype "passive"))
    )
    (net (code "53") (name "Net-(LED4-PadA)") (class "Default")
      (node (ref "LED4") (pin "A") (pinfunction "A_A") (pintype "passive"))
      (node (ref "R8") (pin "1") (pinfunction "1_1") (pintype "passive"))
    )
    (net (code "54") (name "Net-(LED5-PadA)") (class "Default")
      (node (ref "LED5") (pin "A") (pinfunction "A_A") (pintype "passive"))
      (node (ref "R9") (pin "1") (pinfunction "1_1") (pintype "passive"))
    )
    (net (code "55") (name "Net-(LED6-PadA)") (class "Default")
      (node (ref "LED6") (pin "A") (pinfunction "A_A") (pintype "passive"))
      (node (ref "R10") (pin "1") (pinfunction "1_1") (pintype "passive"))
    )
    (net (code "56") (name "Net-(LED7-PadA)") (class "Default")
      (node (ref "LED7") (pin "A") (pinfunction "A_A") (pintype "passive"))
      (node (ref "R11") (pin "1") (pinfunction "1_1") (pintype "passive"))
    )
    (net (code "57") (name "Net-(LED8-PadA)") (class "Default")
      (node (ref "LED8") (pin "A") (pinfunction "A_A") (pintype "passive"))
      (node (ref "R12") (pin "1") (pinfunction "1_1") (pintype "passive"))
    )
    (net (code "58") (name "Net-(LED9-PadA)") (class "Default")
      (node (ref "LED9") (pin "A") (pinfunction "A_A") (pintype "passive"))
      (node (ref "R13") (pin "1") (pinfunction "1_1") (pintype "passive"))
    )
    (net (code "59") (name "Net-(LED10-PadA)") (class "Default")
      (node (ref "LED10") (pin "A") (pinfunction "A_A") (pintype "passive"))
      (node (ref "R27") (pin "2") (pinfunction "2_2") (pintype "passive"))
    )
    (net (code "60") (name "Net-(LED11-PadA)") (class "Default")
      (node (ref "LED11") (pin "A") (pinfunction "A_A") (pintype "passive"))
      (node (ref "R28") (pin "2") (pinfunction "2_2") (pintype "passive"))
    )
    (net (code "61") (name "Net-(Q1-PadB)") (class "Default")
      (node (ref "Q1") (pin "B") (pinfunction "B_B") (pintype "passive"))
      (node (ref "R18") (pin "1") (pinfunction "1_1") (pintype "passive"))
      (node (ref "R20") (pin "2") (pinfunction "2_2") (pintype "passive"))
      (node (ref "R21") (pin "2") (pinfunction "2_2") (pintype "passive"))
    )
    (net (code "62") (name "Net-(Q2-B)") (class "Default")
      (node (ref "C16") (pin "2") (pinfunction "2_2") (pintype "passive"))
      (node (ref "Q2") (pin "1") (pinfunction "B_1") (pintype "passive"))
      (node (ref "R22") (pin "2") (pinfunction "2_2") (pintype "passive"))
      (node (ref "R24") (pin "2") (pinfunction "2_2") (pintype "passive"))
    )
    (net (code "63") (name "Net-(Q2-C)") (class "Default")
      (node (ref "Q2") (pin "2") (pinfunction "C_2") (pintype "passive"))
      (node (ref "Q3") (pin "2") (pinfunction "E_2") (pintype "passive"))
      (node (ref "R30") (pin "2") (pinfunction "2_2") (pintype "passive"))
    )
    (net (code "64") (name "Net-(Q2-E)") (class "Default")
      (node (ref "C14") (pin "1") (pinfunction "1_1") (pintype "passive"))
      (node (ref "C16") (pin "1") (pinfunction "1_1") (pintype "passive"))
      (node (ref "D17") (pin "C") (pinfunction "C_C") (pintype "passive"))
      (node (ref "Q2") (pin "3") (pinfunction "E_3") (pintype "passive"))
      (node (ref "R22") (pin "1") (pinfunction "1_1") (pintype "passive"))
      (node (ref "R23") (pin "2") (pinfunction "2_2") (pintype "passive"))
    )
    (net (code "65") (name "Net-(Q3-B)") (class "Default")
      (node (ref "Q3") (pin "1") (pinfunction "B_1") (pintype "passive"))
      (node (ref "R26") (pin "1") (pinfunction "1_1") (pintype "passive"))
      (node (ref "R29") (pin "1") (pinfunction "1_1") (pintype "passive"))
    )
    (net (code "66") (name "Net-(Q3-C)") (class "Default")
      (node (ref "Q3") (pin "3") (pinfunction "C_3") (pintype "passive"))
      (node (ref "R25") (pin "1") (pinfunction "1_1") (pintype "passive"))
    )
    (net (code "67") (name "Net-(R16-Pad1)") (class "Default")
      (node (ref "R16") (pin "1") (pinfunction "1_1") (pintype "passive"))
      (node (ref "SJ1") (pin "2") (pinfunction "2_2") (pintype "passive"))
    )
    (net (code "68") (name "Net-(S1-P)") (class "Default")
      (node (ref "D1") (pin "A") (pinfunction "A_A") (pintype "passive"))
      (node (ref "S1") (pin "3") (pinfunction "P_3") (pintype "passive"))
    )
    (net (code "69") (name "Net-(S2-P)") (class "Default")
      (node (ref "D2") (pin "A") (pinfunction "A_A") (pintype "passive"))
      (node (ref "S2") (pin "3") (pinfunction "P_3") (pintype "passive"))
    )
    (net (code "70") (name "Net-(S3-P)") (class "Default")
      (node (ref "D3") (pin "A") (pinfunction "A_A") (pintype "passive"))
      (node (ref "S3") (pin "3") (pinfunction "P_3") (pintype "passive"))
    )
    (net (code "71") (name "Net-(S4-P)") (class "Default")
      (node (ref "D4") (pin "A") (pinfunction "A_A") (pintype "passive"))
      (node (ref "S4") (pin "3") (pinfunction "P_3") (pintype "passive"))
    )
    (net (code "72") (name "Net-(S5-P)") (class "Default")
      (node (ref "D5") (pin "A") (pinfunction "A_A") (pintype "passive"))
      (node (ref "S5") (pin "3") (pinfunction "P_3") (pintype "passive"))
    )
    (net (code "73") (name "Net-(S6-P)") (class "Default")
      (node (ref "D6") (pin "A") (pinfunction "A_A") (pintype "passive"))
      (node (ref "S6") (pin "3") (pinfunction "P_3") (pintype "passive"))
    )
    (net (code "74") (name "Net-(S7-P)") (class "Default")
      (node (ref "D7") (pin "A") (pinfunction "A_A") (pintype "passive"))
      (node (ref "S7") (pin "3") (pinfunction "P_3") (pintype "passive"))
    )
    (net (code "75") (name "Net-(S8-P)") (class "Default")
      (node (ref "D8") (pin "A") (pinfunction "A_A") (pintype "passive"))
      (node (ref "S8") (pin "3") (pinfunction "P_3") (pintype "passive"))
    )
    (net (code "76") (name "Net-(U1-XTALIN)") (class "Default")
      (node (ref "C18") (pin "2") (pinfunction "2_2") (pintype "passive"))
      (node (ref "C20") (pin "1") (pinfunction "1_1") (pintype "passive"))
      (node (ref "C22") (pin "1") (pinfunction "1_1") (pintype "passive"))
      (node (ref "U1") (pin "6") (pinfunction "XTALIN_6") (pintype "input"))
      (node (ref "X1") (pin "3") (pinfunction "2_3") (pintype "passive"))
    )
    (net (code "77") (name "Net-(U1-XTALOUT)") (class "Default")
      (node (ref "C21") (pin "1") (pinfunction "1_1") (pintype "passive"))
      (node (ref "U1") (pin "7") (pinfunction "XTALOUT_7") (pintype "output"))
      (node (ref "X1") (pin "1") (pinfunction "1_1") (pintype "passive"))
    )
    (net (code "78") (name "Net-(U2-ADJ)") (class "Default")
      (node (ref "C2") (pin "2") (pinfunction "2_2") (pintype "passive"))
      (node (ref "R2") (pin "1") (pinfunction "1_1") (pintype "passive"))
      (node (ref "R5") (pin "2") (pinfunction "2_2") (pintype "passive"))
      (node (ref "U2") (pin "3") (pinfunction "ADJ_3") (pintype "passive"))
    )
    (net (code "79") (name "Net-(U2-BST)") (class "Default")
      (node (ref "C1") (pin "2") (pinfunction "2_2") (pintype "passive"))
      (node (ref "U2") (pin "1") (pinfunction "BST_1") (pintype "output"))
    )
    (net (code "80") (name "Net-(U2-EN)") (class "Default")
      (node (ref "R1") (pin "2") (pinfunction "2_2") (pintype "passive"))
      (node (ref "R4") (pin "1") (pinfunction "1_1") (pintype "passive"))
      (node (ref "U2") (pin "4") (pinfunction "EN_4") (pintype "input"))
    )
    (net (code "81") (name "Net-(U3-FO)") (class "Default")
      (node (ref "C18") (pin "1") (pinfunction "1_1") (pintype "passive"))
      (node (ref "U3") (pin "3") (pinfunction "FO_3") (pintype "output"))
    )
    (net (code "82") (name "unconnected-(LSP1-PadMP)") (class "Default")
      (node (ref "LSP1") (pin "MP") (pinfunction "MP_MP") (pintype "passive"))
    )
    (net (code "83") (name "unconnected-(LSP2-PadMP)") (class "Default")
      (node (ref "LSP2") (pin "MP") (pinfunction "MP_MP") (pintype "passive"))
    )
    (net (code "84") (name "unconnected-(P2-Pad6)") (class "Default")
      (node (ref "P2") (pin "6") (pinfunction "6_6") (pintype "passive"))
    )
    (net (code "85") (name "unconnected-(P2-Pad8)") (class "Default")
      (node (ref "P2") (pin "8") (pinfunction "8_8") (pintype "passive"))
    )
    (net (code "86") (name "unconnected-(Q2-C{slash}-Pad4)") (class "Default")
      (node (ref "Q2") (pin "4") (pinfunction "C/_4") (pintype "passive"))
    )
    (net (code "87") (name "unconnected-(S1-P1-Pad4)") (class "Default")
      (node (ref "S1") (pin "4") (pinfunction "P1_4") (pintype "passive"))
    )
    (net (code "88") (name "unconnected-(S1-S1-Pad2)") (class "Default")
      (node (ref "S1") (pin "2") (pinfunction "S1_2") (pintype "passive"))
    )
    (net (code "89") (name "unconnected-(S2-P1-Pad4)") (class "Default")
      (node (ref "S2") (pin "4") (pinfunction "P1_4") (pintype "passive"))
    )
    (net (code "90") (name "unconnected-(S2-S1-Pad2)") (class "Default")
      (node (ref "S2") (pin "2") (pinfunction "S1_2") (pintype "passive"))
    )
    (net (code "91") (name "unconnected-(S3-P1-Pad4)") (class "Default")
      (node (ref "S3") (pin "4") (pinfunction "P1_4") (pintype "passive"))
    )
    (net (code "92") (name "unconnected-(S3-S1-Pad2)") (class "Default")
      (node (ref "S3") (pin "2") (pinfunction "S1_2") (pintype "passive"))
    )
    (net (code "93") (name "unconnected-(S4-P1-Pad4)") (class "Default")
      (node (ref "S4") (pin "4") (pinfunction "P1_4") (pintype "passive"))
    )
    (net (code "94") (name "unconnected-(S4-S1-Pad2)") (class "Default")
      (node (ref "S4") (pin "2") (pinfunction "S1_2") (pintype "passive"))
    )
    (net (code "95") (name "unconnected-(S5-P1-Pad4)") (class "Default")
      (node (ref "S5") (pin "4") (pinfunction "P1_4") (pintype "passive"))
    )
    (net (code "96") (name "unconnected-(S5-S1-Pad2)") (class "Default")
      (node (ref "S5") (pin "2") (pinfunction "S1_2") (pintype "passive"))
    )
    (net (code "97") (name "unconnected-(S6-P1-Pad4)") (class "Default")
      (node (ref "S6") (pin "4") (pinfunction "P1_4") (pintype "passive"))
    )
    (net (code "98") (name "unconnected-(S6-S1-Pad2)") (class "Default")
      (node (ref "S6") (pin "2") (pinfunction "S1_2") (pintype "passive"))
    )
    (net (code "99") (name "unconnected-(S7-P1-Pad4)") (class "Default")
      (node (ref "S7") (pin "4") (pinfunction "P1_4") (pintype "passive"))
    )
    (net (code "100") (name "unconnected-(S7-S1-Pad2)") (class "Default")
      (node (ref "S7") (pin "2") (pinfunction "S1_2") (pintype "passive"))
    )
    (net (code "101") (name "unconnected-(S8-P1-Pad4)") (class "Default")
      (node (ref "S8") (pin "4") (pinfunction "P1_4") (pintype "passive"))
    )
    (net (code "102") (name "unconnected-(S8-S1-Pad2)") (class "Default")
      (node (ref "S8") (pin "2") (pinfunction "S1_2") (pintype "passive"))
    )
    (net (code "103") (name "unconnected-(S9-P1-Pad4)") (class "Default")
      (node (ref "S9") (pin "4") (pinfunction "P1_4") (pintype "passive"))
    )
    (net (code "104") (name "unconnected-(S9-S-Pad1)") (class "Default")
      (node (ref "S9") (pin "1") (pinfunction "S_1") (pintype "passive"))
    )
    (net (code "105") (name "unconnected-(S10-P1-Pad4)") (class "Default")
      (node (ref "S10") (pin "4") (pinfunction "P1_4") (pintype "passive"))
    )
    (net (code "106") (name "unconnected-(S10-S-Pad1)") (class "Default")
      (node (ref "S10") (pin "1") (pinfunction "S_1") (pintype "passive"))
    )
    (net (code "107") (name "unconnected-(U1-PIO2_6{slash}CT32B0_MAT1-Pad1)") (class "Default")
      (node (ref "U1") (pin "1") (pinfunction "PIO2_6/CT32B0_MAT1_1") (pintype "bidirectional"))
    )
    (net (code "108") (name "unconnected-(U1-PIO2_7{slash}CT32B0_MAT2{slash}RXD-Pad11)") (class "Default")
      (node (ref "U1") (pin "11") (pinfunction "PIO2_7/CT32B0_MAT2/RXD_11") (pintype "bidirectional"))
    )
    (net (code "109") (name "unconnected-(U1-PIO3_3{slash}RI{slash}CT16B0_CAP0-Pad48)") (class "Default")
      (node (ref "U1") (pin "48") (pinfunction "PIO3_3/RI/CT16B0_CAP0_48") (pintype "bidirectional"))
    )
  )
)
